# Dash22_ENCOD.net
KiCad netlist of a schematic drawn in Altium Designer
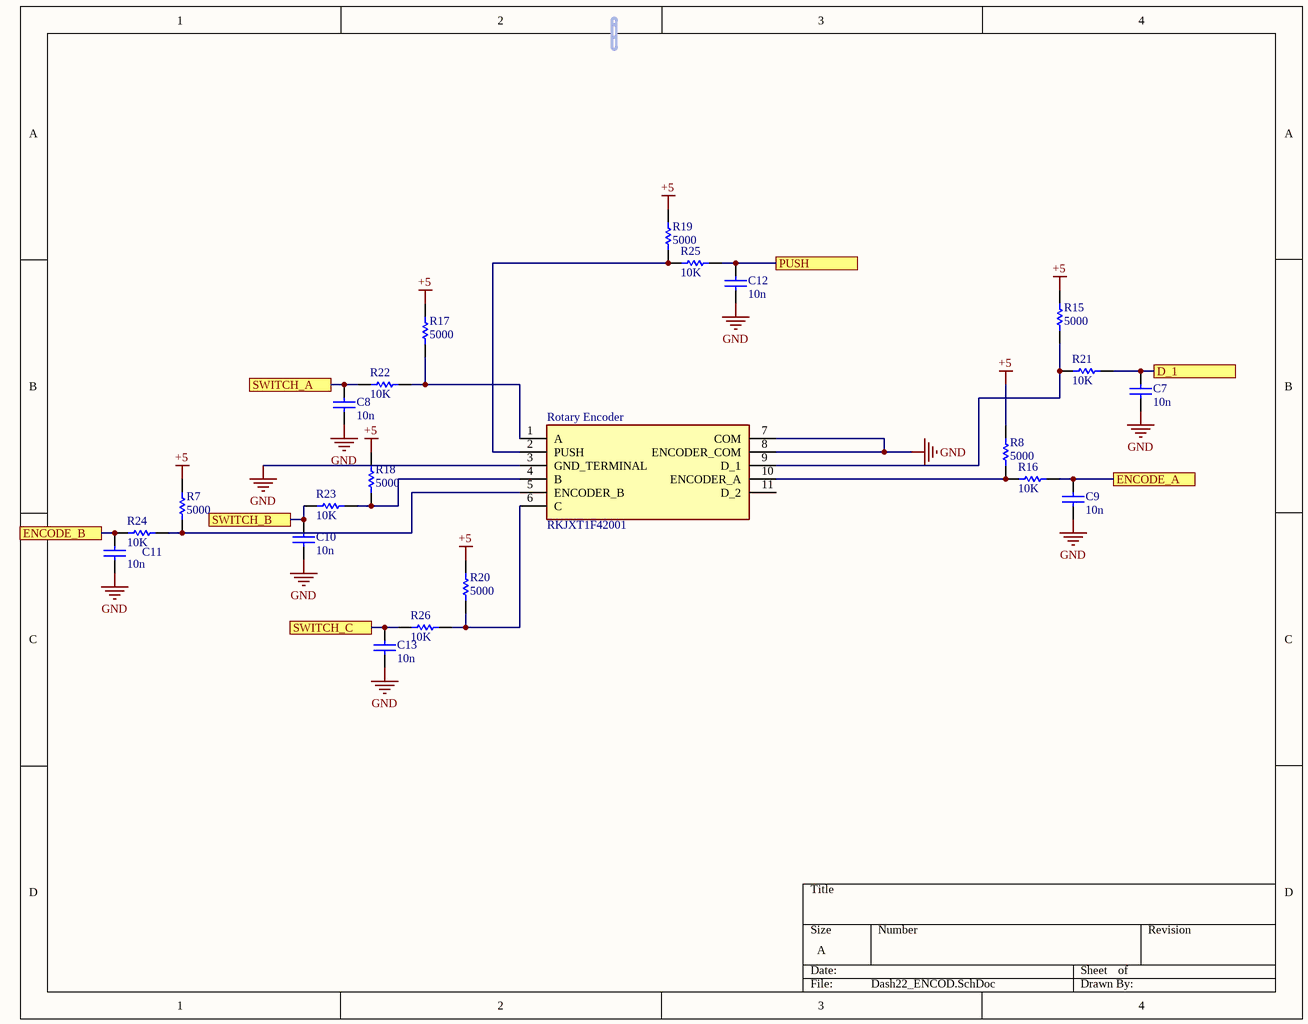
[diagram p0: Dash22_ENCOD.SchDoc]

(export (version "E")
  (design (tool "Eeschema 10.0.6"))
  (components
    (comp (ref "C7")
      (value "10n")
      (footprint "CAPC1608X90X35ML10T15")
      (description "Chip Capacitor, 10 nF, +/- 10%, 50 V, -55 to 125 degC, 0603 (1608 Metric), RoHS, Tape and Reel")
      (fields (field (name "VOLTAGE") "50V") (field (name "TOLERANCE") "10%"))
      (libsource (lib "Altium Content Vault") (part "CAP-NP-2"))
    )
    (comp (ref "C8")
      (value "10n")
      (footprint "CAPC1608X90X35ML10T15")
      (description "Chip Capacitor, 10 nF, +/- 10%, 50 V, -55 to 125 degC, 0603 (1608 Metric), RoHS, Tape and Reel")
      (fields (field (name "VOLTAGE") "50V") (field (name "TOLERANCE") "10%"))
      (libsource (lib "Altium Content Vault") (part "CAP-NP-2"))
    )
    (comp (ref "C9")
      (value "10n")
      (footprint "CAPC1608X90X35ML10T15")
      (description "Chip Capacitor, 10 nF, +/- 10%, 50 V, -55 to 125 degC, 0603 (1608 Metric), RoHS, Tape and Reel")
      (fields (field (name "VOLTAGE") "50V") (field (name "TOLERANCE") "10%"))
      (libsource (lib "Altium Content Vault") (part "CAP-NP-2"))
    )
    (comp (ref "C10")
      (value "10n")
      (footprint "CAPC1608X90X35ML10T15")
      (description "Chip Capacitor, 10 nF, +/- 10%, 50 V, -55 to 125 degC, 0603 (1608 Metric), RoHS, Tape and Reel")
      (fields (field (name "VOLTAGE") "50V") (field (name "TOLERANCE") "10%"))
      (libsource (lib "Altium Content Vault") (part "CAP-NP-2"))
    )
    (comp (ref "C11")
      (value "10n")
      (footprint "CAPC1608X90X35ML10T15")
      (description "Chip Capacitor, 10 nF, +/- 10%, 50 V, -55 to 125 degC, 0603 (1608 Metric), RoHS, Tape and Reel")
      (fields (field (name "VOLTAGE") "50V") (field (name "TOLERANCE") "10%"))
      (libsource (lib "Altium Content Vault") (part "CAP-NP-2"))
    )
    (comp (ref "C12")
      (value "10n")
      (footprint "CAPC1608X90X35ML10T15")
      (description "Chip Capacitor, 10 nF, +/- 10%, 50 V, -55 to 125 degC, 0603 (1608 Metric), RoHS, Tape and Reel")
      (fields (field (name "VOLTAGE") "50V") (field (name "TOLERANCE") "10%"))
      (libsource (lib "Altium Content Vault") (part "CAP-NP-2"))
    )
    (comp (ref "C13")
      (value "10n")
      (footprint "CAPC1608X90X35ML10T15")
      (description "Chip Capacitor, 10 nF, +/- 10%, 50 V, -55 to 125 degC, 0603 (1608 Metric), RoHS, Tape and Reel")
      (fields (field (name "VOLTAGE") "50V") (field (name "TOLERANCE") "10%"))
      (libsource (lib "Altium Content Vault") (part "CAP-NP-2"))
    )
    (comp (ref "R7")
      (value "5000")
      (footprint "RESC1608X55X25ML10T15")
      (description "Chip Resistor, 0 Ohm, 0.1 W, -55 to 155 degC, 0603 (1608 Metric)")
      (libsource (lib "Illini Formula Electric") (part "Symbol"))
    )
    (comp (ref "R8")
      (value "5000")
      (footprint "RESC1608X55X25ML10T15")
      (description "Chip Resistor, 0 Ohm, 0.1 W, -55 to 155 degC, 0603 (1608 Metric)")
      (libsource (lib "Illini Formula Electric") (part "Symbol"))
    )
    (comp (ref "R15")
      (value "5000")
      (footprint "RESC1608X55X25ML10T15")
      (description "Chip Resistor, 0 Ohm, 0.1 W, -55 to 155 degC, 0603 (1608 Metric)")
      (libsource (lib "Illini Formula Electric") (part "Symbol"))
    )
    (comp (ref "R16")
      (value "10K")
      (footprint "RESC1608X55X25ML10T15")
      (description "Chip Resistor, 0 Ohm, 0.1 W, -55 to 155 degC, 0603 (1608 Metric)")
      (libsource (lib "Illini Formula Electric") (part "Symbol"))
    )
    (comp (ref "R17")
      (value "5000")
      (footprint "RESC1608X55X25ML10T15")
      (description "Chip Resistor, 0 Ohm, 0.1 W, -55 to 155 degC, 0603 (1608 Metric)")
      (libsource (lib "Illini Formula Electric") (part "Symbol"))
    )
    (comp (ref "R18")
      (value "5000")
      (footprint "RESC1608X55X25ML10T15")
      (description "Chip Resistor, 0 Ohm, 0.1 W, -55 to 155 degC, 0603 (1608 Metric)")
      (libsource (lib "Illini Formula Electric") (part "Symbol"))
    )
    (comp (ref "R19")
      (value "5000")
      (footprint "RESC1608X55X25ML10T15")
      (description "Chip Resistor, 0 Ohm, 0.1 W, -55 to 155 degC, 0603 (1608 Metric)")
      (libsource (lib "Illini Formula Electric") (part "Symbol"))
    )
    (comp (ref "R20")
      (value "5000")
      (footprint "RESC1608X55X25ML10T15")
      (description "Chip Resistor, 0 Ohm, 0.1 W, -55 to 155 degC, 0603 (1608 Metric)")
      (libsource (lib "Illini Formula Electric") (part "Symbol"))
    )
    (comp (ref "R21")
      (value "10K")
      (footprint "RESC1608X55X25ML10T15")
      (description "Chip Resistor, 0 Ohm, 0.1 W, -55 to 155 degC, 0603 (1608 Metric)")
      (libsource (lib "Illini Formula Electric") (part "Symbol"))
    )
    (comp (ref "R22")
      (value "10K")
      (footprint "RESC1608X55X25ML10T15")
      (description "Chip Resistor, 0 Ohm, 0.1 W, -55 to 155 degC, 0603 (1608 Metric)")
      (libsource (lib "Illini Formula Electric") (part "Symbol"))
    )
    (comp (ref "R23")
      (value "10K")
      (footprint "RESC1608X55X25ML10T15")
      (description "Chip Resistor, 0 Ohm, 0.1 W, -55 to 155 degC, 0603 (1608 Metric)")
      (libsource (lib "Illini Formula Electric") (part "Symbol"))
    )
    (comp (ref "R24")
      (value "10K")
      (footprint "RESC1608X55X25ML10T15")
      (description "Chip Resistor, 0 Ohm, 0.1 W, -55 to 155 degC, 0603 (1608 Metric)")
      (libsource (lib "Illini Formula Electric") (part "Symbol"))
    )
    (comp (ref "R25")
      (value "10K")
      (footprint "RESC1608X55X25ML10T15")
      (description "Chip Resistor, 0 Ohm, 0.1 W, -55 to 155 degC, 0603 (1608 Metric)")
      (libsource (lib "Illini Formula Electric") (part "Symbol"))
    )
    (comp (ref "R26")
      (value "10K")
      (footprint "RESC1608X55X25ML10T15")
      (description "Chip Resistor, 0 Ohm, 0.1 W, -55 to 155 degC, 0603 (1608 Metric)")
      (libsource (lib "Illini Formula Electric") (part "Symbol"))
    )
    (comp (ref "Rotary Encoder")
      (value "RKJXT1F42001")
      (footprint "SamacSys:RKJXT1F42001")
      (description "Switch")
      (fields (field (name "MOUSER PART NUMBER") "688-RKJXT1F42001"))
      (libsource (lib "*") (part "RKJXT1F42001"))
    )
  )
  (nets
    (net (code "1") (name "+5") (class "Default")
      (node (ref "R15") (pin "2") (pinfunction "2_2") (pintype "passive"))
      (node (ref "R17") (pin "2") (pinfunction "2_2") (pintype "passive"))
      (node (ref "R18") (pin "2") (pinfunction "2_2") (pintype "passive"))
      (node (ref "R19") (pin "2") (pinfunction "2_2") (pintype "passive"))
      (node (ref "R20") (pin "2") (pinfunction "2_2") (pintype "passive"))
      (node (ref "R7") (pin "2") (pinfunction "2_2") (pintype "passive"))
      (node (ref "R8") (pin "2") (pinfunction "2_2") (pintype "passive"))
    )
    (net (code "2") (name "/D_1") (class "Default")
      (node (ref "C7") (pin "2") (pinfunction "2_2") (pintype "passive"))
      (node (ref "R21") (pin "2") (pinfunction "2_2") (pintype "passive"))
    )
    (net (code "3") (name "/ENCODE_A") (class "Default")
      (node (ref "C9") (pin "2") (pinfunction "2_2") (pintype "passive"))
      (node (ref "R16") (pin "2") (pinfunction "2_2") (pintype "passive"))
    )
    (net (code "4") (name "/ENCODE_B") (class "Default")
      (node (ref "C11") (pin "2") (pinfunction "2_2") (pintype "passive"))
      (node (ref "R24") (pin "1") (pinfunction "1_1") (pintype "passive"))
    )
    (net (code "5") (name "/PUSH") (class "Default")
      (node (ref "C12") (pin "2") (pinfunction "2_2") (pintype "passive"))
      (node (ref "R25") (pin "2") (pinfunction "2_2") (pintype "passive"))
    )
    (net (code "6") (name "/SWITCH_A") (class "Default")
      (node (ref "C8") (pin "2") (pinfunction "2_2") (pintype "passive"))
      (node (ref "R22") (pin "1") (pinfunction "1_1") (pintype "passive"))
    )
    (net (code "7") (name "/SWITCH_B") (class "Default")
      (node (ref "C10") (pin "2") (pinfunction "2_2") (pintype "passive"))
      (node (ref "R23") (pin "1") (pinfunction "1_1") (pintype "passive"))
    )
    (net (code "8") (name "/SWITCH_C") (class "Default")
      (node (ref "C13") (pin "2") (pinfunction "2_2") (pintype "passive"))
      (node (ref "R26") (pin "1") (pinfunction "1_1") (pintype "passive"))
    )
    (net (code "9") (name "GND") (class "Default")
      (node (ref "C10") (pin "1") (pinfunction "1_1") (pintype "passive"))
      (node (ref "C11") (pin "1") (pinfunction "1_1") (pintype "passive"))
      (node (ref "C12") (pin "1") (pinfunction "1_1") (pintype "passive"))
      (node (ref "C13") (pin "1") (pinfunction "1_1") (pintype "passive"))
      (node (ref "C7") (pin "1") (pinfunction "1_1") (pintype "passive"))
      (node (ref "C8") (pin "1") (pinfunction "1_1") (pintype "passive"))
      (node (ref "C9") (pin "1") (pinfunction "1_1") (pintype "passive"))
      (node (ref "Rotary Encoder") (pin "3") (pinfunction "GND_TERMINAL_3") (pintype "passive"))
      (node (ref "Rotary Encoder") (pin "7") (pinfunction "COM_7") (pintype "passive"))
      (node (ref "Rotary Encoder") (pin "8") (pinfunction "ENCODER_COM_8") (pintype "passive"))
    )
    (net (code "10") (name "Net-(Rotary Encoder-A)") (class "Default")
      (node (ref "R17") (pin "1") (pinfunction "1_1") (pintype "passive"))
      (node (ref "R22") (pin "2") (pinfunction "2_2") (pintype "passive"))
      (node (ref "Rotary Encoder") (pin "1") (pinfunction "A_1") (pintype "passive"))
    )
    (net (code "11") (name "Net-(Rotary Encoder-B)") (class "Default")
      (node (ref "R18") (pin "1") (pinfunction "1_1") (pintype "passive"))
      (node (ref "R23") (pin "2") (pinfunction "2_2") (pintype "passive"))
      (node (ref "Rotary Encoder") (pin "4") (pinfunction "B_4") (pintype "passive"))
    )
    (net (code "12") (name "Net-(Rotary Encoder-C)") (class "Default")
      (node (ref "R20") (pin "1") (pinfunction "1_1") (pintype "passive"))
      (node (ref "R26") (pin "2") (pinfunction "2_2") (pintype "passive"))
      (node (ref "Rotary Encoder") (pin "6") (pinfunction "C_6") (pintype "passive"))
    )
    (net (code "13") (name "Net-(Rotary Encoder-D_1)") (class "Default")
      (node (ref "R15") (pin "1") (pinfunction "1_1") (pintype "passive"))
      (node (ref "R21") (pin "1") (pinfunction "1_1") (pintype "passive"))
      (node (ref "Rotary Encoder") (pin "9") (pinfunction "D_1_9") (pintype "passive"))
    )
    (net (code "14") (name "Net-(Rotary Encoder-ENCODER_A)") (class "Default")
      (node (ref "R16") (pin "1") (pinfunction "1_1") (pintype "passive"))
      (node (ref "R8") (pin "1") (pinfunction "1_1") (pintype "passive"))
      (node (ref "Rotary Encoder") (pin "10") (pinfunction "ENCODER_A_10") (pintype "passive"))
    )
    (net (code "15") (name "Net-(Rotary Encoder-ENCODER_B)") (class "Default")
      (node (ref "R24") (pin "2") (pinfunction "2_2") (pintype "passive"))
      (node (ref "R7") (pin "1") (pinfunction "1_1") (pintype "passive"))
      (node (ref "Rotary Encoder") (pin "5") (pinfunction "ENCODER_B_5") (pintype "passive"))
    )
    (net (code "16") (name "Net-(Rotary Encoder-PUSH)") (class "Default")
      (node (ref "R19") (pin "1") (pinfunction "1_1") (pintype "passive"))
      (node (ref "R25") (pin "1") (pinfunction "1_1") (pintype "passive"))
      (node (ref "Rotary Encoder") (pin "2") (pinfunction "PUSH_2") (pintype "passive"))
    )
    (net (code "17") (name "unconnected-(Rotary Encoder-D_2-Pad11)") (class "Default")
      (node (ref "Rotary Encoder") (pin "11") (pinfunction "D_2_11") (pintype "passive"))
    )
  )
)
